# reed_relay_switcher.net
KiCad netlist of a schematic drawn in EAGLE
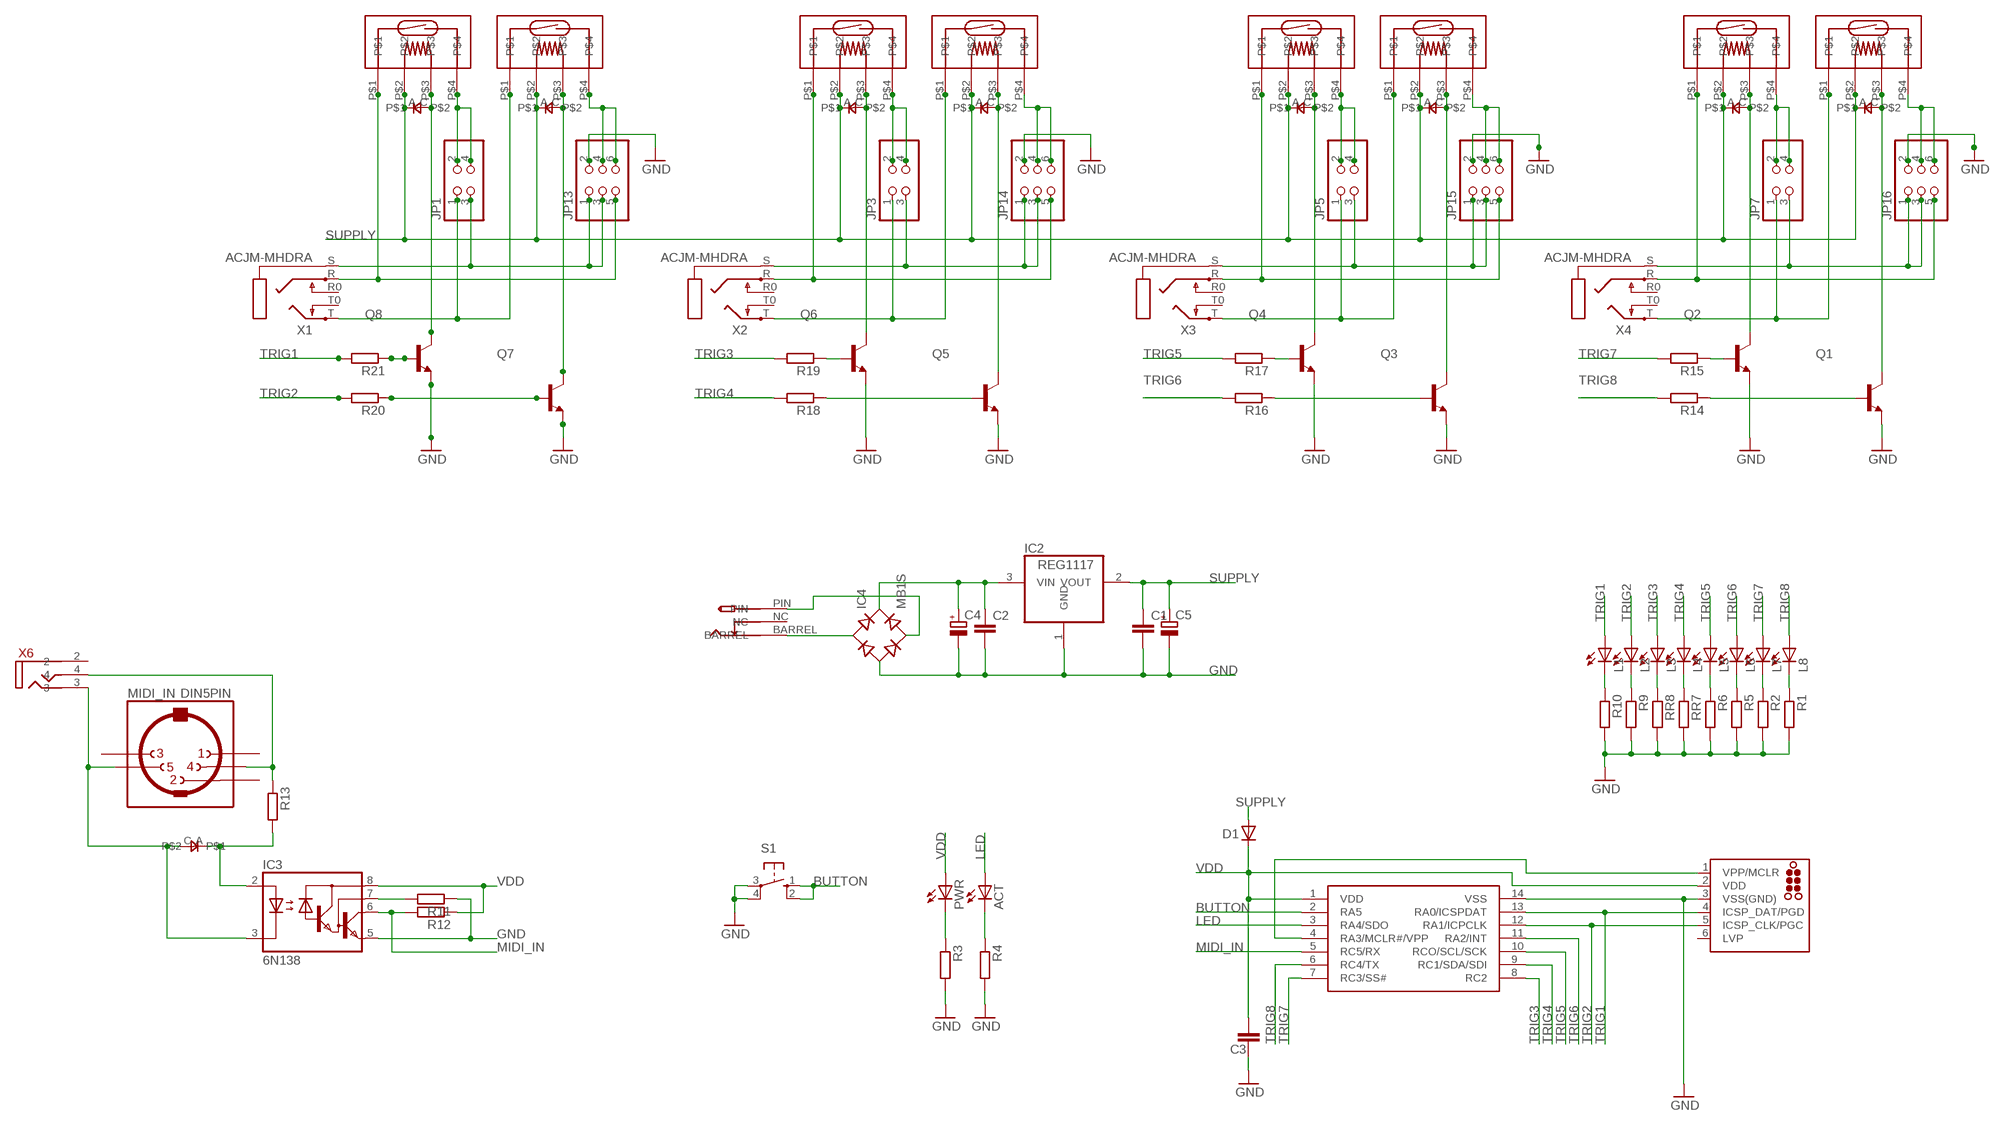
[diagram p0: schematic, sheet 1]

(export (version "E")
  (design (tool "Eeschema 10.0.6"))
  (components
    (comp (ref "ACT")
      (value "LED3MM")
      (footprint "eagle-import:LED3MM")
      (libsource (lib "eagle-import") (part "LED3MM"))
    )
    (comp (ref "C1")
      (value "C-EUC0805")
      (footprint "eagle-import:C0805")
      (libsource (lib "eagle-import") (part "C-EUC0805"))
    )
    (comp (ref "C2")
      (value "C-EUC0805")
      (footprint "eagle-import:C0805")
      (libsource (lib "eagle-import") (part "C-EUC0805"))
    )
    (comp (ref "C3")
      (value "C-EUC0805")
      (footprint "eagle-import:C0805")
      (libsource (lib "eagle-import") (part "C-EUC0805"))
    )
    (comp (ref "C4")
      (value "CPOL-EUE2,5-6E")
      (footprint "eagle-import:E2,5-6E")
      (libsource (lib "eagle-import") (part "CPOL-EUE2,5-6E"))
    )
    (comp (ref "C5")
      (value "CPOL-EUE2,5-6E")
      (footprint "eagle-import:E2,5-6E")
      (libsource (lib "eagle-import") (part "CPOL-EUE2,5-6E"))
    )
    (comp (ref "D1")
      (value "CGRM4001-G")
      (footprint "eagle-import:SOD-123_MINI-SMA")
      (libsource (lib "eagle-import") (part "CGRM400-G1"))
    )
    (comp (ref "D2")
      (value "0805DIODE")
      (footprint "eagle-import:0805DIODE")
      (libsource (lib "eagle-import") (part "0805DIODE"))
    )
    (comp (ref "D3")
      (value "0805DIODE")
      (footprint "eagle-import:0805DIODE")
      (libsource (lib "eagle-import") (part "0805DIODE"))
    )
    (comp (ref "D4")
      (value "0805DIODE")
      (footprint "eagle-import:0805DIODE")
      (libsource (lib "eagle-import") (part "0805DIODE"))
    )
    (comp (ref "D5")
      (value "0805DIODE")
      (footprint "eagle-import:0805DIODE")
      (libsource (lib "eagle-import") (part "0805DIODE"))
    )
    (comp (ref "D6")
      (value "0805DIODE")
      (footprint "eagle-import:0805DIODE")
      (libsource (lib "eagle-import") (part "0805DIODE"))
    )
    (comp (ref "D7")
      (value "0805DIODE")
      (footprint "eagle-import:0805DIODE")
      (libsource (lib "eagle-import") (part "0805DIODE"))
    )
    (comp (ref "D8")
      (value "0805DIODE")
      (footprint "eagle-import:0805DIODE")
      (libsource (lib "eagle-import") (part "0805DIODE"))
    )
    (comp (ref "D9")
      (value "0805DIODE")
      (footprint "eagle-import:0805DIODE")
      (libsource (lib "eagle-import") (part "0805DIODE"))
    )
    (comp (ref "D10")
      (value "0805DIODE")
      (footprint "eagle-import:0805DIODE")
      (libsource (lib "eagle-import") (part "0805DIODE"))
    )
    (comp (ref "IC1")
      (value "PIC16F1825SO14")
      (footprint "eagle-import:SO14")
      (libsource (lib "eagle-import") (part "PIC16F1825SO14"))
    )
    (comp (ref "IC2")
      (value "REG1117")
      (footprint "eagle-import:SOT223")
      (libsource (lib "eagle-import") (part "REG1117"))
    )
    (comp (ref "IC3")
      (value "6N138")
      (footprint "eagle-import:DIL08")
      (fields (field (name "MF") "VISHAY/TELEFUNKEN"))
      (libsource (lib "eagle-import") (part "6N138"))
    )
    (comp (ref "IC4")
      (value "MB1S")
      (footprint "eagle-import:SOIC-4")
      (libsource (lib "eagle-import") (part "MBS1"))
    )
    (comp (ref "ICSP")
      (value "TC2030-MCP-NL")
      (footprint "eagle-import:TC2030-MCP-NL")
      (libsource (lib "eagle-import") (part "TC2030-MCP-NL"))
    )
    (comp (ref "JP1")
      (value "PINHD-2X2")
      (footprint "eagle-import:2X02")
      (libsource (lib "eagle-import") (part "PINHD-2X2"))
    )
    (comp (ref "JP3")
      (value "PINHD-2X2")
      (footprint "eagle-import:2X02")
      (libsource (lib "eagle-import") (part "PINHD-2X2"))
    )
    (comp (ref "JP5")
      (value "PINHD-2X2")
      (footprint "eagle-import:2X02")
      (libsource (lib "eagle-import") (part "PINHD-2X2"))
    )
    (comp (ref "JP7")
      (value "PINHD-2X2")
      (footprint "eagle-import:2X02")
      (libsource (lib "eagle-import") (part "PINHD-2X2"))
    )
    (comp (ref "JP13")
      (value "PINHD-2X3")
      (footprint "eagle-import:2X03")
      (libsource (lib "eagle-import") (part "PINHD-2X3"))
    )
    (comp (ref "JP14")
      (value "PINHD-2X3")
      (footprint "eagle-import:2X03")
      (libsource (lib "eagle-import") (part "PINHD-2X3"))
    )
    (comp (ref "JP15")
      (value "PINHD-2X3")
      (footprint "eagle-import:2X03")
      (libsource (lib "eagle-import") (part "PINHD-2X3"))
    )
    (comp (ref "JP16")
      (value "PINHD-2X3")
      (footprint "eagle-import:2X03")
      (libsource (lib "eagle-import") (part "PINHD-2X3"))
    )
    (comp (ref "L1")
      (value "LED3MM")
      (footprint "eagle-import:LED3MM")
      (libsource (lib "eagle-import") (part "LED3MM"))
    )
    (comp (ref "L2")
      (value "LED3MM")
      (footprint "eagle-import:LED3MM")
      (libsource (lib "eagle-import") (part "LED3MM"))
    )
    (comp (ref "L3")
      (value "LED3MM")
      (footprint "eagle-import:LED3MM")
      (libsource (lib "eagle-import") (part "LED3MM"))
    )
    (comp (ref "L4")
      (value "LED3MM")
      (footprint "eagle-import:LED3MM")
      (libsource (lib "eagle-import") (part "LED3MM"))
    )
    (comp (ref "L5")
      (value "LED3MM")
      (footprint "eagle-import:LED3MM")
      (libsource (lib "eagle-import") (part "LED3MM"))
    )
    (comp (ref "L6")
      (value "LED3MM")
      (footprint "eagle-import:LED3MM")
      (libsource (lib "eagle-import") (part "LED3MM"))
    )
    (comp (ref "L7")
      (value "LED3MM")
      (footprint "eagle-import:LED3MM")
      (libsource (lib "eagle-import") (part "LED3MM"))
    )
    (comp (ref "L8")
      (value "LED3MM")
      (footprint "eagle-import:LED3MM")
      (libsource (lib "eagle-import") (part "LED3MM"))
    )
    (comp (ref "MIDI_IN")
      (value "DIN5PIN")
      (footprint "eagle-import:EDGEDIN")
      (libsource (lib "eagle-import") (part "DIN5PIN"))
    )
    (comp (ref "PWR")
      (value "LED3MM")
      (footprint "eagle-import:LED3MM")
      (libsource (lib "eagle-import") (part "LED3MM"))
    )
    (comp (ref "Q1")
      (value "MMBT3904LT1-NPN-SOT23-BEC")
      (footprint "eagle-import:SOT23-BEC")
      (libsource (lib "eagle-import") (part "-NPN-SOT23-BECMMBT3904LT1"))
    )
    (comp (ref "Q2")
      (value "MMBT3904LT1-NPN-SOT23-BEC")
      (footprint "eagle-import:SOT23-BEC")
      (libsource (lib "eagle-import") (part "-NPN-SOT23-BECMMBT3904LT1"))
    )
    (comp (ref "Q3")
      (value "MMBT3904LT1-NPN-SOT23-BEC")
      (footprint "eagle-import:SOT23-BEC")
      (libsource (lib "eagle-import") (part "-NPN-SOT23-BECMMBT3904LT1"))
    )
    (comp (ref "Q4")
      (value "MMBT3904LT1-NPN-SOT23-BEC")
      (footprint "eagle-import:SOT23-BEC")
      (libsource (lib "eagle-import") (part "-NPN-SOT23-BECMMBT3904LT1"))
    )
    (comp (ref "Q5")
      (value "MMBT3904LT1-NPN-SOT23-BEC")
      (footprint "eagle-import:SOT23-BEC")
      (libsource (lib "eagle-import") (part "-NPN-SOT23-BECMMBT3904LT1"))
    )
    (comp (ref "Q6")
      (value "MMBT3904LT1-NPN-SOT23-BEC")
      (footprint "eagle-import:SOT23-BEC")
      (libsource (lib "eagle-import") (part "-NPN-SOT23-BECMMBT3904LT1"))
    )
    (comp (ref "Q7")
      (value "MMBT3904LT1-NPN-SOT23-BEC")
      (footprint "eagle-import:SOT23-BEC")
      (libsource (lib "eagle-import") (part "-NPN-SOT23-BECMMBT3904LT1"))
    )
    (comp (ref "Q8")
      (value "MMBT3904LT1-NPN-SOT23-BEC")
      (footprint "eagle-import:SOT23-BEC")
      (libsource (lib "eagle-import") (part "-NPN-SOT23-BECMMBT3904LT1"))
    )
    (comp (ref "R1")
      (value "R-EU_R0805")
      (footprint "eagle-import:R0805")
      (libsource (lib "eagle-import") (part "R-EU_R0805"))
    )
    (comp (ref "R2")
      (value "R-EU_R0805")
      (footprint "eagle-import:R0805")
      (libsource (lib "eagle-import") (part "R-EU_R0805"))
    )
    (comp (ref "R3")
      (value "R-EU_R0805")
      (footprint "eagle-import:R0805")
      (libsource (lib "eagle-import") (part "R-EU_R0805"))
    )
    (comp (ref "R4")
      (value "R-EU_R0805")
      (footprint "eagle-import:R0805")
      (libsource (lib "eagle-import") (part "R-EU_R0805"))
    )
    (comp (ref "R5")
      (value "R-EU_R0805")
      (footprint "eagle-import:R0805")
      (libsource (lib "eagle-import") (part "R-EU_R0805"))
    )
    (comp (ref "R6")
      (value "R-EU_R0805")
      (footprint "eagle-import:R0805")
      (libsource (lib "eagle-import") (part "R-EU_R0805"))
    )
    (comp (ref "R9")
      (value "R-EU_R0805")
      (footprint "eagle-import:R0805")
      (libsource (lib "eagle-import") (part "R-EU_R0805"))
    )
    (comp (ref "R10")
      (value "R-EU_R0805")
      (footprint "eagle-import:R0805")
      (libsource (lib "eagle-import") (part "R-EU_R0805"))
    )
    (comp (ref "R11")
      (value "R-EU_R0805")
      (footprint "eagle-import:R0805")
      (libsource (lib "eagle-import") (part "R-EU_R0805"))
    )
    (comp (ref "R12")
      (value "R-EU_R0805")
      (footprint "eagle-import:R0805")
      (libsource (lib "eagle-import") (part "R-EU_R0805"))
    )
    (comp (ref "R13")
      (value "R-EU_R0805")
      (footprint "eagle-import:R0805")
      (libsource (lib "eagle-import") (part "R-EU_R0805"))
    )
    (comp (ref "R14")
      (value "R-EU_R0805")
      (footprint "eagle-import:R0805")
      (libsource (lib "eagle-import") (part "R-EU_R0805"))
    )
    (comp (ref "R15")
      (value "R-EU_R0805")
      (footprint "eagle-import:R0805")
      (libsource (lib "eagle-import") (part "R-EU_R0805"))
    )
    (comp (ref "R16")
      (value "R-EU_R0805")
      (footprint "eagle-import:R0805")
      (libsource (lib "eagle-import") (part "R-EU_R0805"))
    )
    (comp (ref "R17")
      (value "R-EU_R0805")
      (footprint "eagle-import:R0805")
      (libsource (lib "eagle-import") (part "R-EU_R0805"))
    )
    (comp (ref "R18")
      (value "R-EU_R0805")
      (footprint "eagle-import:R0805")
      (libsource (lib "eagle-import") (part "R-EU_R0805"))
    )
    (comp (ref "R19")
      (value "R-EU_R0805")
      (footprint "eagle-import:R0805")
      (libsource (lib "eagle-import") (part "R-EU_R0805"))
    )
    (comp (ref "R20")
      (value "R-EU_R0805")
      (footprint "eagle-import:R0805")
      (libsource (lib "eagle-import") (part "R-EU_R0805"))
    )
    (comp (ref "R21")
      (value "R-EU_R0805")
      (footprint "eagle-import:R0805")
      (libsource (lib "eagle-import") (part "R-EU_R0805"))
    )
    (comp (ref "RLY1")
      (value "9007-REED-RELAY")
      (footprint "eagle-import:9007-REED-RELAY")
      (libsource (lib "eagle-import") (part "9007-REED-RELAY"))
    )
    (comp (ref "RLY2")
      (value "9007-REED-RELAY")
      (footprint "eagle-import:9007-REED-RELAY")
      (libsource (lib "eagle-import") (part "9007-REED-RELAY"))
    )
    (comp (ref "RLY3")
      (value "9007-REED-RELAY")
      (footprint "eagle-import:9007-REED-RELAY")
      (libsource (lib "eagle-import") (part "9007-REED-RELAY"))
    )
    (comp (ref "RLY4")
      (value "9007-REED-RELAY")
      (footprint "eagle-import:9007-REED-RELAY")
      (libsource (lib "eagle-import") (part "9007-REED-RELAY"))
    )
    (comp (ref "RLY5")
      (value "9007-REED-RELAY")
      (footprint "eagle-import:9007-REED-RELAY")
      (libsource (lib "eagle-import") (part "9007-REED-RELAY"))
    )
    (comp (ref "RLY6")
      (value "9007-REED-RELAY")
      (footprint "eagle-import:9007-REED-RELAY")
      (libsource (lib "eagle-import") (part "9007-REED-RELAY"))
    )
    (comp (ref "RLY7")
      (value "9007-REED-RELAY")
      (footprint "eagle-import:9007-REED-RELAY")
      (libsource (lib "eagle-import") (part "9007-REED-RELAY"))
    )
    (comp (ref "RLY8")
      (value "9007-REED-RELAY")
      (footprint "eagle-import:9007-REED-RELAY")
      (libsource (lib "eagle-import") (part "9007-REED-RELAY"))
    )
    (comp (ref "RR7")
      (value "R-EU_R0805")
      (footprint "eagle-import:R0805")
      (libsource (lib "eagle-import") (part "R-EU_R0805"))
    )
    (comp (ref "RR8")
      (value "R-EU_R0805")
      (footprint "eagle-import:R0805")
      (libsource (lib "eagle-import") (part "R-EU_R0805"))
    )
    (comp (ref "S1")
      (value "10-XX")
      (footprint "eagle-import:B3F-10XX")
      (fields (field (name "MPN") "B3F-1000"))
      (libsource (lib "eagle-import") (part "10-XX"))
    )
    (comp (ref "U$9")
      (value "PWR_SOCKET_2_1MM")
      (footprint "eagle-import:PWR_SOCKET_2_1MM")
      (libsource (lib "eagle-import") (part "PWR_SOCKET_2_1MM"))
    )
    (comp (ref "X1")
      (value "ACJM-MHDRA")
      (footprint "eagle-import:ACJM-MHDR")
      (libsource (lib "eagle-import") (part "ACJM-MHDRA"))
    )
    (comp (ref "X2")
      (value "ACJM-MHDRA")
      (footprint "eagle-import:ACJM-MHDR")
      (libsource (lib "eagle-import") (part "ACJM-MHDRA"))
    )
    (comp (ref "X3")
      (value "ACJM-MHDRA")
      (footprint "eagle-import:ACJM-MHDR")
      (libsource (lib "eagle-import") (part "ACJM-MHDRA"))
    )
    (comp (ref "X4")
      (value "ACJM-MHDRA")
      (footprint "eagle-import:ACJM-MHDR")
      (libsource (lib "eagle-import") (part "ACJM-MHDRA"))
    )
    (comp (ref "X6")
      (value "VERTICAL_3_5MM_SOCKET")
      (footprint "eagle-import:VERTICAL_3_5MM_SOCKET")
      (libsource (lib "eagle-import") (part "VERTICAL_3_5MM_SOCKET"))
    )
  )
  (nets
    (net (code "1") (name "/BUTTON") (class "Default")
      (node (ref "IC1") (pin "2") (pinfunction "RA5_2") (pintype "bidirectional"))
      (node (ref "S1") (pin "1") (pinfunction "S_1") (pintype "passive"))
      (node (ref "S1") (pin "2") (pinfunction "S1_2") (pintype "passive"))
    )
    (net (code "2") (name "/LED") (class "Default")
      (node (ref "ACT") (pin "A") (pinfunction "A_A") (pintype "passive"))
      (node (ref "IC1") (pin "3") (pinfunction "RA4/SDO_3") (pintype "bidirectional"))
    )
    (net (code "3") (name "/MIDI_IN") (class "Default")
      (node (ref "IC1") (pin "5") (pinfunction "RC5/RX_5") (pintype "bidirectional"))
      (node (ref "IC3") (pin "6") (pinfunction "VO_6") (pintype "passive"))
      (node (ref "R12") (pin "2") (pinfunction "2_2") (pintype "passive"))
    )
    (net (code "4") (name "/SUPPLY") (class "Default")
      (node (ref "C1") (pin "1") (pinfunction "1_1") (pintype "passive"))
      (node (ref "C5") (pin "+") (pinfunction "+_+") (pintype "passive"))
      (node (ref "D1") (pin "A") (pinfunction "A_A") (pintype "passive"))
      (node (ref "D10") (pin "A") (pinfunction "P$2_A") (pintype "bidirectional"))
      (node (ref "D3") (pin "A") (pinfunction "P$2_A") (pintype "bidirectional"))
      (node (ref "D4") (pin "A") (pinfunction "P$2_A") (pintype "bidirectional"))
      (node (ref "D5") (pin "A") (pinfunction "P$2_A") (pintype "bidirectional"))
      (node (ref "D6") (pin "A") (pinfunction "P$2_A") (pintype "bidirectional"))
      (node (ref "D7") (pin "A") (pinfunction "P$2_A") (pintype "bidirectional"))
      (node (ref "D8") (pin "A") (pinfunction "P$2_A") (pintype "bidirectional"))
      (node (ref "D9") (pin "A") (pinfunction "P$2_A") (pintype "bidirectional"))
      (node (ref "IC2") (pin "2") (pinfunction "VOUT_2") (pintype "output"))
      (node (ref "RLY1") (pin "P$2") (pinfunction "P$2_P$2") (pintype "bidirectional"))
      (node (ref "RLY2") (pin "P$2") (pinfunction "P$2_P$2") (pintype "bidirectional"))
      (node (ref "RLY3") (pin "P$2") (pinfunction "P$2_P$2") (pintype "bidirectional"))
      (node (ref "RLY4") (pin "P$2") (pinfunction "P$2_P$2") (pintype "bidirectional"))
      (node (ref "RLY5") (pin "P$2") (pinfunction "P$2_P$2") (pintype "bidirectional"))
      (node (ref "RLY6") (pin "P$2") (pinfunction "P$2_P$2") (pintype "bidirectional"))
      (node (ref "RLY7") (pin "P$2") (pinfunction "P$2_P$2") (pintype "bidirectional"))
      (node (ref "RLY8") (pin "P$2") (pinfunction "P$2_P$2") (pintype "bidirectional"))
    )
    (net (code "5") (name "/TRIG1") (class "Default")
      (node (ref "IC1") (pin "13") (pinfunction "RA0/ICSPDAT_13") (pintype "bidirectional"))
      (node (ref "ICSP") (pin "4") (pinfunction "ICSP_DAT/PGD_4") (pintype "bidirectional"))
      (node (ref "L1") (pin "A") (pinfunction "A_A") (pintype "passive"))
      (node (ref "R21") (pin "2") (pinfunction "2_2") (pintype "passive"))
    )
    (net (code "6") (name "/TRIG2") (class "Default")
      (node (ref "IC1") (pin "12") (pinfunction "RA1/ICPCLK_12") (pintype "bidirectional"))
      (node (ref "ICSP") (pin "5") (pinfunction "ICSP_CLK/PGC_5") (pintype "output"))
      (node (ref "L2") (pin "A") (pinfunction "A_A") (pintype "passive"))
      (node (ref "R20") (pin "2") (pinfunction "2_2") (pintype "passive"))
    )
    (net (code "7") (name "/TRIG3") (class "Default")
      (node (ref "IC1") (pin "8") (pinfunction "RC2_8") (pintype "bidirectional"))
      (node (ref "L3") (pin "A") (pinfunction "A_A") (pintype "passive"))
      (node (ref "R19") (pin "2") (pinfunction "2_2") (pintype "passive"))
    )
    (net (code "8") (name "/TRIG4") (class "Default")
      (node (ref "IC1") (pin "9") (pinfunction "RC1/SDA/SDI_9") (pintype "bidirectional"))
      (node (ref "L4") (pin "A") (pinfunction "A_A") (pintype "passive"))
      (node (ref "R18") (pin "2") (pinfunction "2_2") (pintype "passive"))
    )
    (net (code "9") (name "/TRIG5") (class "Default")
      (node (ref "IC1") (pin "10") (pinfunction "RCO/SCL/SCK_10") (pintype "bidirectional"))
      (node (ref "L5") (pin "A") (pinfunction "A_A") (pintype "passive"))
      (node (ref "R17") (pin "2") (pinfunction "2_2") (pintype "passive"))
    )
    (net (code "10") (name "/TRIG6") (class "Default")
      (node (ref "IC1") (pin "11") (pinfunction "RA2/INT_11") (pintype "bidirectional"))
      (node (ref "L6") (pin "A") (pinfunction "A_A") (pintype "passive"))
      (node (ref "R16") (pin "2") (pinfunction "2_2") (pintype "passive"))
    )
    (net (code "11") (name "/TRIG7") (class "Default")
      (node (ref "IC1") (pin "7") (pinfunction "RC3/SS#_7") (pintype "bidirectional"))
      (node (ref "L7") (pin "A") (pinfunction "A_A") (pintype "passive"))
      (node (ref "R15") (pin "2") (pinfunction "2_2") (pintype "passive"))
    )
    (net (code "12") (name "/TRIG8") (class "Default")
      (node (ref "IC1") (pin "6") (pinfunction "RC4/TX_6") (pintype "bidirectional"))
      (node (ref "L8") (pin "A") (pinfunction "A_A") (pintype "passive"))
      (node (ref "R14") (pin "2") (pinfunction "2_2") (pintype "passive"))
    )
    (net (code "13") (name "/VDD") (class "Default")
      (node (ref "C3") (pin "1") (pinfunction "1_1") (pintype "passive"))
      (node (ref "D1") (pin "C") (pinfunction "C_C") (pintype "passive"))
      (node (ref "IC1") (pin "1") (pinfunction "VDD_1") (pintype "power_in"))
      (node (ref "IC3") (pin "8") (pinfunction "VCC_8") (pintype "passive"))
      (node (ref "ICSP") (pin "2") (pinfunction "VDD_2") (pintype "power_in"))
      (node (ref "PWR") (pin "A") (pinfunction "A_A") (pintype "passive"))
      (node (ref "R12") (pin "1") (pinfunction "1_1") (pintype "passive"))
    )
    (net (code "14") (name "GND") (class "Default")
      (node (ref "C1") (pin "2") (pinfunction "2_2") (pintype "passive"))
      (node (ref "C2") (pin "2") (pinfunction "2_2") (pintype "passive"))
      (node (ref "C3") (pin "2") (pinfunction "2_2") (pintype "passive"))
      (node (ref "C4") (pin "-") (pinfunction "-_-") (pintype "passive"))
      (node (ref "C5") (pin "-") (pinfunction "-_-") (pintype "passive"))
      (node (ref "IC1") (pin "14") (pinfunction "VSS_14") (pintype "power_in"))
      (node (ref "IC2") (pin "1") (pinfunction "GND_1") (pintype "power_in"))
      (node (ref "IC3") (pin "5") (pinfunction "GND_5") (pintype "passive"))
      (node (ref "IC4") (pin "-") (pinfunction "-_-") (pintype "passive"))
      (node (ref "ICSP") (pin "3") (pinfunction "VSS(GND)_3") (pintype "power_in"))
      (node (ref "JP13") (pin "2") (pinfunction "2_2") (pintype "passive"))
      (node (ref "JP14") (pin "2") (pinfunction "2_2") (pintype "passive"))
      (node (ref "JP15") (pin "2") (pinfunction "2_2") (pintype "passive"))
      (node (ref "JP16") (pin "2") (pinfunction "2_2") (pintype "passive"))
      (node (ref "Q1") (pin "E") (pinfunction "E_E") (pintype "passive"))
      (node (ref "Q2") (pin "E") (pinfunction "E_E") (pintype "passive"))
      (node (ref "Q3") (pin "E") (pinfunction "E_E") (pintype "passive"))
      (node (ref "Q4") (pin "E") (pinfunction "E_E") (pintype "passive"))
      (node (ref "Q5") (pin "E") (pinfunction "E_E") (pintype "passive"))
      (node (ref "Q6") (pin "E") (pinfunction "E_E") (pintype "passive"))
      (node (ref "Q7") (pin "E") (pinfunction "E_E") (pintype "passive"))
      (node (ref "Q8") (pin "E") (pinfunction "E_E") (pintype "passive"))
      (node (ref "R1") (pin "2") (pinfunction "2_2") (pintype "passive"))
      (node (ref "R10") (pin "2") (pinfunction "2_2") (pintype "passive"))
      (node (ref "R11") (pin "1") (pinfunction "1_1") (pintype "passive"))
      (node (ref "R2") (pin "2") (pinfunction "2_2") (pintype "passive"))
      (node (ref "R3") (pin "2") (pinfunction "2_2") (pintype "passive"))
      (node (ref "R4") (pin "2") (pinfunction "2_2") (pintype "passive"))
      (node (ref "R5") (pin "2") (pinfunction "2_2") (pintype "passive"))
      (node (ref "R6") (pin "2") (pinfunction "2_2") (pintype "passive"))
      (node (ref "R9") (pin "2") (pinfunction "2_2") (pintype "passive"))
      (node (ref "RR7") (pin "2") (pinfunction "2_2") (pintype "passive"))
      (node (ref "RR8") (pin "2") (pinfunction "2_2") (pintype "passive"))
      (node (ref "S1") (pin "3") (pinfunction "P_3") (pintype "passive"))
      (node (ref "S1") (pin "4") (pinfunction "P1_4") (pintype "passive"))
    )
    (net (code "15") (name "Net-(ACT-C)") (class "Default")
      (node (ref "ACT") (pin "K") (pinfunction "C_K") (pintype "passive"))
      (node (ref "R4") (pin "1") (pinfunction "1_1") (pintype "passive"))
    )
    (net (code "16") (name "Net-(D2-P$1)") (class "Default")
      (node (ref "D2") (pin "C") (pinfunction "P$1_C") (pintype "bidirectional"))
      (node (ref "IC3") (pin "3") (pinfunction "C_3") (pintype "passive"))
      (node (ref "MIDI_IN") (pin "5") (pinfunction "5_5") (pintype "passive"))
      (node (ref "X6") (pin "3") (pinfunction "3_3") (pintype "bidirectional"))
    )
    (net (code "17") (name "Net-(D2-P$2)") (class "Default")
      (node (ref "D2") (pin "A") (pinfunction "P$2_A") (pintype "bidirectional"))
      (node (ref "IC3") (pin "2") (pinfunction "A_2") (pintype "passive"))
      (node (ref "R13") (pin "2") (pinfunction "2_2") (pintype "passive"))
    )
    (net (code "18") (name "Net-(D3-P$1)") (class "Default")
      (node (ref "D3") (pin "C") (pinfunction "P$1_C") (pintype "bidirectional"))
      (node (ref "Q1") (pin "C") (pinfunction "C_C") (pintype "passive"))
      (node (ref "RLY8") (pin "P$3") (pinfunction "P$3_P$3") (pintype "bidirectional"))
    )
    (net (code "19") (name "Net-(D4-P$1)") (class "Default")
      (node (ref "D4") (pin "C") (pinfunction "P$1_C") (pintype "bidirectional"))
      (node (ref "Q2") (pin "C") (pinfunction "C_C") (pintype "passive"))
      (node (ref "RLY7") (pin "P$3") (pinfunction "P$3_P$3") (pintype "bidirectional"))
    )
    (net (code "20") (name "Net-(D5-P$1)") (class "Default")
      (node (ref "D5") (pin "C") (pinfunction "P$1_C") (pintype "bidirectional"))
      (node (ref "Q3") (pin "C") (pinfunction "C_C") (pintype "passive"))
      (node (ref "RLY6") (pin "P$3") (pinfunction "P$3_P$3") (pintype "bidirectional"))
    )
    (net (code "21") (name "Net-(D6-P$1)") (class "Default")
      (node (ref "D6") (pin "C") (pinfunction "P$1_C") (pintype "bidirectional"))
      (node (ref "Q4") (pin "C") (pinfunction "C_C") (pintype "passive"))
      (node (ref "RLY5") (pin "P$3") (pinfunction "P$3_P$3") (pintype "bidirectional"))
    )
    (net (code "22") (name "Net-(D7-P$1)") (class "Default")
      (node (ref "D7") (pin "C") (pinfunction "P$1_C") (pintype "bidirectional"))
      (node (ref "Q5") (pin "C") (pinfunction "C_C") (pintype "passive"))
      (node (ref "RLY4") (pin "P$3") (pinfunction "P$3_P$3") (pintype "bidirectional"))
    )
    (net (code "23") (name "Net-(D8-P$1)") (class "Default")
      (node (ref "D8") (pin "C") (pinfunction "P$1_C") (pintype "bidirectional"))
      (node (ref "Q6") (pin "C") (pinfunction "C_C") (pintype "passive"))
      (node (ref "RLY3") (pin "P$3") (pinfunction "P$3_P$3") (pintype "bidirectional"))
    )
    (net (code "24") (name "Net-(D9-P$1)") (class "Default")
      (node (ref "D9") (pin "C") (pinfunction "P$1_C") (pintype "bidirectional"))
      (node (ref "Q7") (pin "C") (pinfunction "C_C") (pintype "passive"))
      (node (ref "RLY2") (pin "P$3") (pinfunction "P$3_P$3") (pintype "bidirectional"))
    )
    (net (code "25") (name "Net-(D10-P$1)") (class "Default")
      (node (ref "D10") (pin "C") (pinfunction "P$1_C") (pintype "bidirectional"))
      (node (ref "Q8") (pin "C") (pinfunction "C_C") (pintype "passive"))
      (node (ref "RLY1") (pin "P$3") (pinfunction "P$3_P$3") (pintype "bidirectional"))
    )
    (net (code "26") (name "Net-(IC1-RA3{slash}MCLR#{slash}VPP)") (class "Default")
      (node (ref "IC1") (pin "4") (pinfunction "RA3/MCLR#/VPP_4") (pintype "input"))
      (node (ref "ICSP") (pin "1") (pinfunction "VPP/MCLR_1") (pintype "passive"))
    )
    (net (code "27") (name "Net-(IC2-VIN)") (class "Default")
      (node (ref "C2") (pin "1") (pinfunction "1_1") (pintype "passive"))
      (node (ref "C4") (pin "+") (pinfunction "+_+") (pintype "passive"))
      (node (ref "IC2") (pin "3") (pinfunction "VIN_3") (pintype "input"))
      (node (ref "IC4") (pin "+") (pinfunction "+_+") (pintype "passive"))
    )
    (net (code "28") (name "Net-(IC3-VB)") (class "Default")
      (node (ref "IC3") (pin "7") (pinfunction "VB_7") (pintype "passive"))
      (node (ref "R11") (pin "2") (pinfunction "2_2") (pintype "passive"))
    )
    (net (code "29") (name "Net-(IC4-AC1)") (class "Default")
      (node (ref "IC4") (pin "~1") (pinfunction "AC1_~1") (pintype "passive"))
      (node (ref "U$9") (pin "BARREL") (pinfunction "BARREL_BARREL") (pintype "bidirectional"))
    )
    (net (code "30") (name "Net-(IC4-AC2)") (class "Default")
      (node (ref "IC4") (pin "~2") (pinfunction "AC2_~2") (pintype "passive"))
      (node (ref "U$9") (pin "PIN") (pinfunction "PIN_PIN") (pintype "bidirectional"))
    )
    (net (code "31") (name "Net-(JP1-Pad2)") (class "Default")
      (node (ref "JP1") (pin "2") (pinfunction "2_2") (pintype "passive"))
      (node (ref "JP1") (pin "4") (pinfunction "4_4") (pintype "passive"))
      (node (ref "RLY1") (pin "P$4") (pinfunction "P$4_P$4") (pintype "bidirectional"))
    )
    (net (code "32") (name "Net-(JP3-Pad2)") (class "Default")
      (node (ref "JP3") (pin "2") (pinfunction "2_2") (pintype "passive"))
      (node (ref "JP3") (pin "4") (pinfunction "4_4") (pintype "passive"))
      (node (ref "RLY3") (pin "P$4") (pinfunction "P$4_P$4") (pintype "bidirectional"))
    )
    (net (code "33") (name "Net-(JP5-Pad2)") (class "Default")
      (node (ref "JP5") (pin "2") (pinfunction "2_2") (pintype "passive"))
      (node (ref "JP5") (pin "4") (pinfunction "4_4") (pintype "passive"))
      (node (ref "RLY5") (pin "P$4") (pinfunction "P$4_P$4") (pintype "bidirectional"))
    )
    (net (code "34") (name "Net-(JP7-Pad2)") (class "Default")
      (node (ref "JP7") (pin "2") (pinfunction "2_2") (pintype "passive"))
      (node (ref "JP7") (pin "4") (pinfunction "4_4") (pintype "passive"))
      (node (ref "RLY7") (pin "P$4") (pinfunction "P$4_P$4") (pintype "bidirectional"))
    )
    (net (code "35") (name "Net-(JP13-Pad4)") (class "Default")
      (node (ref "JP13") (pin "4") (pinfunction "4_4") (pintype "passive"))
      (node (ref "JP13") (pin "6") (pinfunction "6_6") (pintype "passive"))
      (node (ref "RLY2") (pin "P$4") (pinfunction "P$4_P$4") (pintype "bidirectional"))
    )
    (net (code "36") (name "Net-(JP14-Pad4)") (class "Default")
      (node (ref "JP14") (pin "4") (pinfunction "4_4") (pintype "passive"))
      (node (ref "JP14") (pin "6") (pinfunction "6_6") (pintype "passive"))
      (node (ref "RLY4") (pin "P$4") (pinfunction "P$4_P$4") (pintype "bidirectional"))
    )
    (net (code "37") (name "Net-(JP15-Pad4)") (class "Default")
      (node (ref "JP15") (pin "4") (pinfunction "4_4") (pintype "passive"))
      (node (ref "JP15") (pin "6") (pinfunction "6_6") (pintype "passive"))
      (node (ref "RLY6") (pin "P$4") (pinfunction "P$4_P$4") (pintype "bidirectional"))
    )
    (net (code "38") (name "Net-(JP16-Pad4)") (class "Default")
      (node (ref "JP16") (pin "4") (pinfunction "4_4") (pintype "passive"))
      (node (ref "JP16") (pin "6") (pinfunction "6_6") (pintype "passive"))
      (node (ref "RLY8") (pin "P$4") (pinfunction "P$4_P$4") (pintype "bidirectional"))
    )
    (net (code "39") (name "Net-(L1-C)") (class "Default")
      (node (ref "L1") (pin "K") (pinfunction "C_K") (pintype "passive"))
      (node (ref "R10") (pin "1") (pinfunction "1_1") (pintype "passive"))
    )
    (net (code "40") (name "Net-(L2-C)") (class "Default")
      (node (ref "L2") (pin "K") (pinfunction "C_K") (pintype "passive"))
      (node (ref "R9") (pin "1") (pinfunction "1_1") (pintype "passive"))
    )
    (net (code "41") (name "Net-(L3-C)") (class "Default")
      (node (ref "L3") (pin "K") (pinfunction "C_K") (pintype "passive"))
      (node (ref "RR8") (pin "1") (pinfunction "1_1") (pintype "passive"))
    )
    (net (code "42") (name "Net-(L4-C)") (class "Default")
      (node (ref "L4") (pin "K") (pinfunction "C_K") (pintype "passive"))
      (node (ref "RR7") (pin "1") (pinfunction "1_1") (pintype "passive"))
    )
    (net (code "43") (name "Net-(L5-C)") (class "Default")
      (node (ref "L5") (pin "K") (pinfunction "C_K") (pintype "passive"))
      (node (ref "R6") (pin "1") (pinfunction "1_1") (pintype "passive"))
    )
    (net (code "44") (name "Net-(L6-C)") (class "Default")
      (node (ref "L6") (pin "K") (pinfunction "C_K") (pintype "passive"))
      (node (ref "R5") (pin "1") (pinfunction "1_1") (pintype "passive"))
    )
    (net (code "45") (name "Net-(L7-C)") (class "Default")
      (node (ref "L7") (pin "K") (pinfunction "C_K") (pintype "passive"))
      (node (ref "R2") (pin "1") (pinfunction "1_1") (pintype "passive"))
    )
    (net (code "46") (name "Net-(L8-C)") (class "Default")
      (node (ref "L8") (pin "K") (pinfunction "C_K") (pintype "passive"))
      (node (ref "R1") (pin "1") (pinfunction "1_1") (pintype "passive"))
    )
    (net (code "47") (name "Net-(MIDI_IN-Pad4)") (class "Default")
      (node (ref "MIDI_IN") (pin "4") (pinfunction "4_4") (pintype "passive"))
      (node (ref "R13") (pin "1") (pinfunction "1_1") (pintype "passive"))
      (node (ref "X6") (pin "4") (pinfunction "4_4") (pintype "bidirectional"))
    )
    (net (code "48") (name "Net-(PWR-C)") (class "Default")
      (node (ref "PWR") (pin "K") (pinfunction "C_K") (pintype "passive"))
      (node (ref "R3") (pin "1") (pinfunction "1_1") (pintype "passive"))
    )
    (net (code "49") (name "Net-(Q1-PadB)") (class "Default")
      (node (ref "Q1") (pin "B") (pinfunction "B_B") (pintype "passive"))
      (node (ref "R14") (pin "1") (pinfunction "1_1") (pintype "passive"))
    )
    (net (code "50") (name "Net-(Q2-PadB)") (class "Default")
      (node (ref "Q2") (pin "B") (pinfunction "B_B") (pintype "passive"))
      (node (ref "R15") (pin "1") (pinfunction "1_1") (pintype "passive"))
    )
    (net (code "51") (name "Net-(Q3-PadB)") (class "Default")
      (node (ref "Q3") (pin "B") (pinfunction "B_B") (pintype "passive"))
      (node (ref "R16") (pin "1") (pinfunction "1_1") (pintype "passive"))
    )
    (net (code "52") (name "Net-(Q4-PadB)") (class "Default")
      (node (ref "Q4") (pin "B") (pinfunction "B_B") (pintype "passive"))
      (node (ref "R17") (pin "1") (pinfunction "1_1") (pintype "passive"))
    )
    (net (code "53") (name "Net-(Q5-PadB)") (class "Default")
      (node (ref "Q5") (pin "B") (pinfunction "B_B") (pintype "passive"))
      (node (ref "R18") (pin "1") (pinfunction "1_1") (pintype "passive"))
    )
    (net (code "54") (name "Net-(Q6-PadB)") (class "Default")
      (node (ref "Q6") (pin "B") (pinfunction "B_B") (pintype "passive"))
      (node (ref "R19") (pin "1") (pinfunction "1_1") (pintype "passive"))
    )
    (net (code "55") (name "Net-(Q7-PadB)") (class "Default")
      (node (ref "Q7") (pin "B") (pinfunction "B_B") (pintype "passive"))
      (node (ref "R20") (pin "1") (pinfunction "1_1") (pintype "passive"))
    )
    (net (code "56") (name "Net-(Q8-PadB)") (class "Default")
      (node (ref "Q8") (pin "B") (pinfunction "B_B") (pintype "passive"))
      (node (ref "R21") (pin "1") (pinfunction "1_1") (pintype "passive"))
    )
    (net (code "57") (name "Net-(X1-1)") (class "Default")
      (node (ref "JP1") (pin "3") (pinfunction "3_3") (pintype "passive"))
      (node (ref "JP13") (pin "1") (pinfunction "1_1") (pintype "passive"))
      (node (ref "JP13") (pin "3") (pinfunction "3_3") (pintype "passive"))
      (node (ref "X1") (pin "S") (pinfunction "1_S") (pintype "passive"))
    )
    (net (code "58") (name "Net-(X1-2)") (class "Default")
      (node (ref "JP13") (pin "5") (pinfunction "5_5") (pintype "passive"))
      (node (ref "RLY1") (pin "P$1") (pinfunction "P$1_P$1") (pintype "bidirectional"))
      (node (ref "X1") (pin "R") (pinfunction "2_R") (pintype "passive"))
    )
    (net (code "59") (name "Net-(X1-5)") (class "Default")
      (node (ref "JP1") (pin "1") (pinfunction "1_1") (pintype "passive"))
      (node (ref "RLY2") (pin "P$1") (pinfunction "P$1_P$1") (pintype "bidirectional"))
      (node (ref "X1") (pin "T") (pinfunction "5_T") (pintype "passive"))
    )
    (net (code "60") (name "Net-(X2-1)") (class "Default")
      (node (ref "JP14") (pin "1") (pinfunction "1_1") (pintype "passive"))
      (node (ref "JP14") (pin "3") (pinfunction "3_3") (pintype "passive"))
      (node (ref "JP3") (pin "3") (pinfunction "3_3") (pintype "passive"))
      (node (ref "X2") (pin "S") (pinfunction "1_S") (pintype "passive"))
    )
    (net (code "61") (name "Net-(X2-2)") (class "Default")
      (node (ref "JP14") (pin "5") (pinfunction "5_5") (pintype "passive"))
      (node (ref "RLY3") (pin "P$1") (pinfunction "P$1_P$1") (pintype "bidirectional"))
      (node (ref "X2") (pin "R") (pinfunction "2_R") (pintype "passive"))
    )
    (net (code "62") (name "Net-(X2-5)") (class "Default")
      (node (ref "JP3") (pin "1") (pinfunction "1_1") (pintype "passive"))
      (node (ref "RLY4") (pin "P$1") (pinfunction "P$1_P$1") (pintype "bidirectional"))
      (node (ref "X2") (pin "T") (pinfunction "5_T") (pintype "passive"))
    )
    (net (code "63") (name "Net-(X3-1)") (class "Default")
      (node (ref "JP15") (pin "1") (pinfunction "1_1") (pintype "passive"))
      (node (ref "JP15") (pin "3") (pinfunction "3_3") (pintype "passive"))
      (node (ref "JP5") (pin "3") (pinfunction "3_3") (pintype "passive"))
      (node (ref "X3") (pin "S") (pinfunction "1_S") (pintype "passive"))
    )
    (net (code "64") (name "Net-(X3-2)") (class "Default")
      (node (ref "JP15") (pin "5") (pinfunction "5_5") (pintype "passive"))
      (node (ref "RLY5") (pin "P$1") (pinfunction "P$1_P$1") (pintype "bidirectional"))
      (node (ref "X3") (pin "R") (pinfunction "2_R") (pintype "passive"))
    )
    (net (code "65") (name "Net-(X3-5)") (class "Default")
      (node (ref "JP5") (pin "1") (pinfunction "1_1") (pintype "passive"))
      (node (ref "RLY6") (pin "P$1") (pinfunction "P$1_P$1") (pintype "bidirectional"))
      (node (ref "X3") (pin "T") (pinfunction "5_T") (pintype "passive"))
    )
    (net (code "66") (name "Net-(X4-1)") (class "Default")
      (node (ref "JP16") (pin "1") (pinfunction "1_1") (pintype "passive"))
      (node (ref "JP16") (pin "3") (pinfunction "3_3") (pintype "passive"))
      (node (ref "JP7") (pin "3") (pinfunction "3_3") (pintype "passive"))
      (node (ref "X4") (pin "S") (pinfunction "1_S") (pintype "passive"))
    )
    (net (code "67") (name "Net-(X4-2)") (class "Default")
      (node (ref "JP16") (pin "5") (pinfunction "5_5") (pintype "passive"))
      (node (ref "RLY7") (pin "P$1") (pinfunction "P$1_P$1") (pintype "bidirectional"))
      (node (ref "X4") (pin "R") (pinfunction "2_R") (pintype "passive"))
    )
    (net (code "68") (name "Net-(X4-5)") (class "Default")
      (node (ref "JP7") (pin "1") (pinfunction "1_1") (pintype "passive"))
      (node (ref "RLY8") (pin "P$1") (pinfunction "P$1_P$1") (pintype "bidirectional"))
      (node (ref "X4") (pin "T") (pinfunction "5_T") (pintype "passive"))
    )
    (net (code "69") (name "unconnected-(ICSP-LVP-Pad6)") (class "Default")
      (node (ref "ICSP") (pin "6") (pinfunction "LVP_6") (pintype "bidirectional"))
    )
    (net (code "70") (name "unconnected-(MIDI_IN-Pad1)") (class "Default")
      (node (ref "MIDI_IN") (pin "1") (pinfunction "1_1") (pintype "passive"))
    )
    (net (code "71") (name "unconnected-(MIDI_IN-Pad2)") (class "Default")
      (node (ref "MIDI_IN") (pin "2") (pinfunction "2_2") (pintype "passive"))
    )
    (net (code "72") (name "unconnected-(MIDI_IN-Pad3)") (class "Default")
      (node (ref "MIDI_IN") (pin "3") (pinfunction "3_3") (pintype "passive"))
    )
    (net (code "73") (name "unconnected-(U$9-PadNC)") (class "Default")
      (node (ref "U$9") (pin "NC") (pinfunction "NC_NC") (pintype "bidirectional"))
    )
    (net (code "74") (name "unconnected-(X1-3-PadR0)") (class "Default")
      (node (ref "X1") (pin "R0") (pinfunction "3_R0") (pintype "passive"))
    )
    (net (code "75") (name "unconnected-(X1-4-PadT0)") (class "Default")
      (node (ref "X1") (pin "T0") (pinfunction "4_T0") (pintype "passive"))
    )
    (net (code "76") (name "unconnected-(X2-3-PadR0)") (class "Default")
      (node (ref "X2") (pin "R0") (pinfunction "3_R0") (pintype "passive"))
    )
    (net (code "77") (name "unconnected-(X2-4-PadT0)") (class "Default")
      (node (ref "X2") (pin "T0") (pinfunction "4_T0") (pintype "passive"))
    )
    (net (code "78") (name "unconnected-(X3-3-PadR0)") (class "Default")
      (node (ref "X3") (pin "R0") (pinfunction "3_R0") (pintype "passive"))
    )
    (net (code "79") (name "unconnected-(X3-4-PadT0)") (class "Default")
      (node (ref "X3") (pin "T0") (pinfunction "4_T0") (pintype "passive"))
    )
    (net (code "80") (name "unconnected-(X4-3-PadR0)") (class "Default")
      (node (ref "X4") (pin "R0") (pinfunction "3_R0") (pintype "passive"))
    )
    (net (code "81") (name "unconnected-(X4-4-PadT0)") (class "Default")
      (node (ref "X4") (pin "T0") (pinfunction "4_T0") (pintype "passive"))
    )
    (net (code "82") (name "unconnected-(X6-Pad2)") (class "Default")
      (node (ref "X6") (pin "2") (pinfunction "2_2") (pintype "bidirectional"))
    )
  )
)
